# Sheet1.net
KiCad netlist of a schematic drawn in Altium Designer
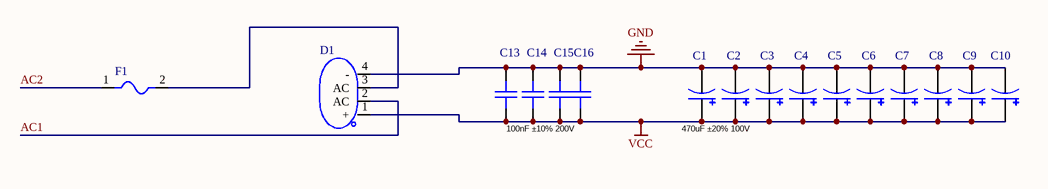
[diagram p0: Sheet1.SchDoc]

(export (version "E")
  (design (tool "Eeschema 10.0.6"))
  (components
    (comp (ref "C1")
      (value "~")
      (footprint "CAP-TH_BD16.0-P7.50-D1.2-FD")
      (fields
        (field (name "LCSC PART NAME") "470uF ±20% 100V")
        (field (name "MANUFACTURER") "CapXon(台湾丰宾)")
        (field (name "MANUFACTURER PART") "KF471M100J250A")
        (field (name "TOLERANCE") "±20%")
      )
      (libsource (lib "altium-import") (part "root_1_KF471M100J250A_"))
    )
    (comp (ref "C2")
      (value "~")
      (footprint "CAP-TH_BD16.0-P7.50-D1.2-FD")
      (fields
        (field (name "MANUFACTURER") "CapXon(台湾丰宾)")
        (field (name "MANUFACTURER PART") "KF471M100J250A")
        (field (name "TOLERANCE") "±20%")
      )
      (libsource (lib "altium-import") (part "root_1_KF471M100J250A_"))
    )
    (comp (ref "C3")
      (value "~")
      (footprint "CAP-TH_BD16.0-P7.50-D1.2-FD")
      (fields
        (field (name "MANUFACTURER") "CapXon(台湾丰宾)")
        (field (name "MANUFACTURER PART") "KF471M100J250A")
        (field (name "TOLERANCE") "±20%")
      )
      (libsource (lib "altium-import") (part "root_1_KF471M100J250A_"))
    )
    (comp (ref "C4")
      (value "~")
      (footprint "CAP-TH_BD16.0-P7.50-D1.2-FD")
      (fields
        (field (name "MANUFACTURER") "CapXon(台湾丰宾)")
        (field (name "MANUFACTURER PART") "KF471M100J250A")
        (field (name "TOLERANCE") "±20%")
      )
      (libsource (lib "altium-import") (part "root_1_KF471M100J250A_"))
    )
    (comp (ref "C5")
      (value "~")
      (footprint "CAP-TH_BD16.0-P7.50-D1.2-FD")
      (fields
        (field (name "MANUFACTURER") "CapXon(台湾丰宾)")
        (field (name "MANUFACTURER PART") "KF471M100J250A")
        (field (name "TOLERANCE") "±20%")
      )
      (libsource (lib "altium-import") (part "root_1_KF471M100J250A_"))
    )
    (comp (ref "C6")
      (value "~")
      (footprint "CAP-TH_BD16.0-P7.50-D1.2-FD")
      (fields
        (field (name "MANUFACTURER") "CapXon(台湾丰宾)")
        (field (name "MANUFACTURER PART") "KF471M100J250A")
        (field (name "TOLERANCE") "±20%")
      )
      (libsource (lib "altium-import") (part "root_1_KF471M100J250A_"))
    )
    (comp (ref "C7")
      (value "~")
      (footprint "CAP-TH_BD16.0-P7.50-D1.2-FD")
      (fields
        (field (name "MANUFACTURER") "CapXon(台湾丰宾)")
        (field (name "MANUFACTURER PART") "KF471M100J250A")
        (field (name "TOLERANCE") "±20%")
      )
      (libsource (lib "altium-import") (part "root_1_KF471M100J250A_"))
    )
    (comp (ref "C8")
      (value "~")
      (footprint "CAP-TH_BD16.0-P7.50-D1.2-FD")
      (fields
        (field (name "MANUFACTURER") "CapXon(台湾丰宾)")
        (field (name "MANUFACTURER PART") "KF471M100J250A")
        (field (name "TOLERANCE") "±20%")
      )
      (libsource (lib "altium-import") (part "root_1_KF471M100J250A_"))
    )
    (comp (ref "C9")
      (value "~")
      (footprint "CAP-TH_BD16.0-P7.50-D1.2-FD")
      (fields
        (field (name "MANUFACTURER") "CapXon(台湾丰宾)")
        (field (name "MANUFACTURER PART") "KF471M100J250A")
        (field (name "TOLERANCE") "±20%")
      )
      (libsource (lib "altium-import") (part "root_1_KF471M100J250A_"))
    )
    (comp (ref "C10")
      (value "~")
      (footprint "CAP-TH_BD16.0-P7.50-D1.2-FD")
      (fields
        (field (name "MANUFACTURER") "CapXon(台湾丰宾)")
        (field (name "MANUFACTURER PART") "KF471M100J250A")
        (field (name "TOLERANCE") "±20%")
      )
      (libsource (lib "altium-import") (part "root_1_KF471M100J250A_"))
    )
    (comp (ref "C13")
      (value "~")
      (footprint "C1206")
      (fields
        (field (name "LCSC PART NAME") "100nF ±10% 200V")
        (field (name "MANUFACTURER") "YAGEO(国巨)")
        (field (name "MANUFACTURER PART") "CC1206KKX7RABB104")
        (field (name "TOLERANCE") "±10%")
      )
      (libsource (lib "altium-import") (part "root_0_CC1206KKX7RABB104_"))
    )
    (comp (ref "C14")
      (value "~")
      (footprint "C1206")
      (fields
        (field (name "MANUFACTURER") "YAGEO(国巨)")
        (field (name "MANUFACTURER PART") "CC1206KKX7RABB104")
        (field (name "TOLERANCE") "±10%")
      )
      (libsource (lib "altium-import") (part "root_0_CC1206KKX7RABB104_"))
    )
    (comp (ref "C15")
      (value "~")
      (footprint "C1206")
      (fields
        (field (name "MANUFACTURER") "YAGEO(国巨)")
        (field (name "MANUFACTURER PART") "CC1206KKX7RABB104")
        (field (name "TOLERANCE") "±10%")
      )
      (libsource (lib "altium-import") (part "root_0_CC1206KKX7RABB104_"))
    )
    (comp (ref "C16")
      (value "~")
      (footprint "C1206")
      (fields
        (field (name "MANUFACTURER") "YAGEO(国巨)")
        (field (name "MANUFACTURER PART") "CC1206KKX7RABB104")
        (field (name "TOLERANCE") "±10%")
      )
      (libsource (lib "altium-import") (part "root_0_CC1206KKX7RABB104_"))
    )
    (comp (ref "D1")
      (value "~")
      (footprint "GBU_4P-L22.0-W3.6-P5.08")
      (fields (field (name "MANUFACTURER") "晶导微电子") (field (name "MANUFACTURER PART") "GBU801"))
      (libsource (lib "altium-import") (part "root_2_GBU801_"))
    )
    (comp (ref "F1")
      (value "~")
      (footprint "F2410")
      (fields (field (name "MANUFACTURER") "JDTfuse集电通") (field (name "MANUFACTURER PART") "JFC2410-1800FS"))
      (libsource (lib "altium-import") (part "root_0_JFC2410-1800FS_"))
    )
  )
  (nets
    (net (code "1") (name "/AC1") (class "Default")
      (node (ref "D1") (pin "2") (pinfunction "AC_2") (pintype "passive"))
    )
    (net (code "2") (name "/AC2") (class "Default")
      (node (ref "F1") (pin "1") (pinfunction "1_1") (pintype "passive"))
    )
    (net (code "3") (name "GND") (class "Default")
      (node (ref "C1") (pin "2") (pinfunction "2_2") (pintype "passive"))
      (node (ref "C10") (pin "2") (pinfunction "2_2") (pintype "passive"))
      (node (ref "C13") (pin "2") (pinfunction "2_2") (pintype "passive"))
      (node (ref "C14") (pin "2") (pinfunction "2_2") (pintype "passive"))
      (node (ref "C15") (pin "2") (pinfunction "2_2") (pintype "passive"))
      (node (ref "C16") (pin "2") (pinfunction "2_2") (pintype "passive"))
      (node (ref "C2") (pin "2") (pinfunction "2_2") (pintype "passive"))
      (node (ref "C3") (pin "2") (pinfunction "2_2") (pintype "passive"))
      (node (ref "C4") (pin "2") (pinfunction "2_2") (pintype "passive"))
      (node (ref "C5") (pin "2") (pinfunction "2_2") (pintype "passive"))
      (node (ref "C6") (pin "2") (pinfunction "2_2") (pintype "passive"))
      (node (ref "C7") (pin "2") (pinfunction "2_2") (pintype "passive"))
      (node (ref "C8") (pin "2") (pinfunction "2_2") (pintype "passive"))
      (node (ref "C9") (pin "2") (pinfunction "2_2") (pintype "passive"))
      (node (ref "D1") (pin "4") (pinfunction "-_4") (pintype "passive"))
    )
    (net (code "4") (name "Net-(D1-AC-Pad3)") (class "Default")
      (node (ref "D1") (pin "3") (pinfunction "AC_3") (pintype "passive"))
      (node (ref "F1") (pin "2") (pinfunction "2_2") (pintype "passive"))
    )
    (net (code "5") (name "VCC") (class "Default")
      (node (ref "C1") (pin "1") (pinfunction "1_1") (pintype "passive"))
      (node (ref "C10") (pin "1") (pinfunction "1_1") (pintype "passive"))
      (node (ref "C13") (pin "1") (pinfunction "1_1") (pintype "passive"))
      (node (ref "C14") (pin "1") (pinfunction "1_1") (pintype "passive"))
      (node (ref "C15") (pin "1") (pinfunction "1_1") (pintype "passive"))
      (node (ref "C16") (pin "1") (pinfunction "1_1") (pintype "passive"))
      (node (ref "C2") (pin "1") (pinfunction "1_1") (pintype "passive"))
      (node (ref "C3") (pin "1") (pinfunction "1_1") (pintype "passive"))
      (node (ref "C4") (pin "1") (pinfunction "1_1") (pintype "passive"))
      (node (ref "C5") (pin "1") (pinfunction "1_1") (pintype "passive"))
      (node (ref "C6") (pin "1") (pinfunction "1_1") (pintype "passive"))
      (node (ref "C7") (pin "1") (pinfunction "1_1") (pintype "passive"))
      (node (ref "C8") (pin "1") (pinfunction "1_1") (pintype "passive"))
      (node (ref "C9") (pin "1") (pinfunction "1_1") (pintype "passive"))
      (node (ref "D1") (pin "1") (pinfunction "+_1") (pintype "passive"))
    )
  )
)
